# deska.net
KiCad netlist of a schematic drawn in EAGLE
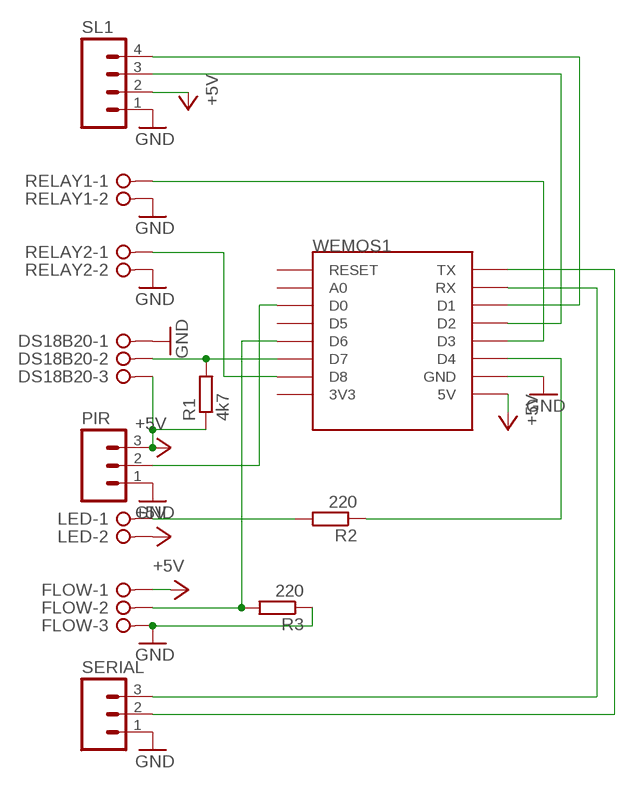
[diagram p0: schematic, sheet 1]

(export (version "E")
  (design (tool "Eeschema 10.0.6"))
  (components
    (comp (ref "DS18B20")
      (value "W237-03P")
      (footprint "eagle-import:W237-133")
      (libsource (lib "eagle-import") (part "W237-03P"))
    )
    (comp (ref "FLOW")
      (value "W237-03P")
      (footprint "eagle-import:W237-133")
      (libsource (lib "eagle-import") (part "W237-03P"))
    )
    (comp (ref "LED")
      (value "W237-02P")
      (footprint "eagle-import:W237-132")
      (libsource (lib "eagle-import") (part "W237-02P"))
    )
    (comp (ref "PIR")
      (value "M03")
      (footprint "eagle-import:03P")
      (libsource (lib "eagle-import") (part "M03"))
    )
    (comp (ref "R1")
      (value "4k7")
      (footprint "eagle-import:0207_10")
      (libsource (lib "eagle-import") (part "R-EU_0207/10"))
    )
    (comp (ref "R2")
      (value "220")
      (footprint "eagle-import:0207_10")
      (libsource (lib "eagle-import") (part "R-EU_0207/10"))
    )
    (comp (ref "R3")
      (value "220")
      (footprint "eagle-import:0207_10")
      (libsource (lib "eagle-import") (part "R-EU_0207/10"))
    )
    (comp (ref "RELAY1")
      (value "W237-02P")
      (footprint "eagle-import:W237-132")
      (libsource (lib "eagle-import") (part "W237-02P"))
    )
    (comp (ref "RELAY2")
      (value "W237-02P")
      (footprint "eagle-import:W237-132")
      (libsource (lib "eagle-import") (part "W237-02P"))
    )
    (comp (ref "SERIAL")
      (value "M03")
      (footprint "eagle-import:03P")
      (libsource (lib "eagle-import") (part "M03"))
    )
    (comp (ref "SL1")
      (value "M04")
      (footprint "eagle-import:04P")
      (libsource (lib "eagle-import") (part "M04"))
    )
    (comp (ref "WEMOS1")
      (value "WEMOS-D1-MINI")
      (footprint "eagle-import:WEMOS-D1-MINI")
      (libsource (lib "eagle-import") (part "WEMOS-D1-MINI"))
    )
  )
  (nets
    (net (code "1") (name "+5V") (class "Default")
      (node (ref "DS18B20") (pin "3") (pinfunction "KL_3") (pintype "passive"))
      (node (ref "FLOW") (pin "1") (pinfunction "KL_1") (pintype "passive"))
      (node (ref "LED") (pin "2") (pinfunction "KL_2") (pintype "passive"))
      (node (ref "PIR") (pin "3") (pinfunction "3_3") (pintype "passive"))
      (node (ref "R1") (pin "1") (pinfunction "1_1") (pintype "passive"))
      (node (ref "SL1") (pin "2") (pinfunction "2_2") (pintype "passive"))
      (node (ref "WEMOS1") (pin "5V") (pinfunction "5V_5V") (pintype "bidirectional"))
    )
    (net (code "2") (name "GND") (class "Default")
      (node (ref "DS18B20") (pin "1") (pinfunction "KL_1") (pintype "passive"))
      (node (ref "FLOW") (pin "3") (pinfunction "KL_3") (pintype "passive"))
      (node (ref "PIR") (pin "1") (pinfunction "1_1") (pintype "passive"))
      (node (ref "R3") (pin "1") (pinfunction "1_1") (pintype "passive"))
      (node (ref "RELAY1") (pin "2") (pinfunction "KL_2") (pintype "passive"))
      (node (ref "RELAY2") (pin "2") (pinfunction "KL_2") (pintype "passive"))
      (node (ref "SERIAL") (pin "1") (pinfunction "1_1") (pintype "passive"))
      (node (ref "SL1") (pin "1") (pinfunction "1_1") (pintype "passive"))
      (node (ref "WEMOS1") (pin "GND") (pinfunction "GND_GND") (pintype "bidirectional"))
    )
    (net (code "3") (name "Net-(DS18B20B-KL)") (class "Default")
      (node (ref "DS18B20") (pin "2") (pinfunction "KL_2") (pintype "passive"))
      (node (ref "R1") (pin "2") (pinfunction "2_2") (pintype "passive"))
      (node (ref "WEMOS1") (pin "D7") (pinfunction "D7_D7") (pintype "bidirectional"))
    )
    (net (code "4") (name "Net-(FLOWB-KL)") (class "Default")
      (node (ref "FLOW") (pin "2") (pinfunction "KL_2") (pintype "passive"))
      (node (ref "R3") (pin "2") (pinfunction "2_2") (pintype "passive"))
      (node (ref "WEMOS1") (pin "D6") (pinfunction "D6_D6") (pintype "bidirectional"))
    )
    (net (code "5") (name "Net-(LEDA-KL)") (class "Default")
      (node (ref "LED") (pin "1") (pinfunction "KL_1") (pintype "passive"))
      (node (ref "R2") (pin "2") (pinfunction "2_2") (pintype "passive"))
    )
    (net (code "6") (name "Net-(PIR-Pad2)") (class "Default")
      (node (ref "PIR") (pin "2") (pinfunction "2_2") (pintype "passive"))
      (node (ref "WEMOS1") (pin "D0") (pinfunction "D0_D0") (pintype "bidirectional"))
    )
    (net (code "7") (name "Net-(R2-Pad1)") (class "Default")
      (node (ref "R2") (pin "1") (pinfunction "1_1") (pintype "passive"))
      (node (ref "WEMOS1") (pin "D4") (pinfunction "D4_D4") (pintype "bidirectional"))
    )
    (net (code "8") (name "Net-(RELAY1A-KL)") (class "Default")
      (node (ref "RELAY1") (pin "1") (pinfunction "KL_1") (pintype "passive"))
      (node (ref "WEMOS1") (pin "D3") (pinfunction "D3_D3") (pintype "bidirectional"))
    )
    (net (code "9") (name "Net-(RELAY2A-KL)") (class "Default")
      (node (ref "RELAY2") (pin "1") (pinfunction "KL_1") (pintype "passive"))
      (node (ref "WEMOS1") (pin "D8") (pinfunction "D8_D8") (pintype "bidirectional"))
    )
    (net (code "10") (name "Net-(SERIAL-Pad2)") (class "Default")
      (node (ref "SERIAL") (pin "2") (pinfunction "2_2") (pintype "passive"))
      (node (ref "WEMOS1") (pin "TX") (pinfunction "TX_TX") (pintype "bidirectional"))
    )
    (net (code "11") (name "Net-(SERIAL-Pad3)") (class "Default")
      (node (ref "SERIAL") (pin "3") (pinfunction "3_3") (pintype "passive"))
      (node (ref "WEMOS1") (pin "RX") (pinfunction "RX_RX") (pintype "bidirectional"))
    )
    (net (code "12") (name "Net-(SL1-Pad3)") (class "Default")
      (node (ref "SL1") (pin "3") (pinfunction "3_3") (pintype "passive"))
      (node (ref "WEMOS1") (pin "D2") (pinfunction "D2_D2") (pintype "bidirectional"))
    )
    (net (code "13") (name "Net-(SL1-Pad4)") (class "Default")
      (node (ref "SL1") (pin "4") (pinfunction "4_4") (pintype "passive"))
      (node (ref "WEMOS1") (pin "D1") (pinfunction "D1_D1") (pintype "bidirectional"))
    )
    (net (code "14") (name "unconnected-(WEMOS1-Pad3V3)") (class "Default")
      (node (ref "WEMOS1") (pin "3V3") (pinfunction "3V3_3V3") (pintype "bidirectional"))
    )
    (net (code "15") (name "unconnected-(WEMOS1-PadA0)") (class "Default")
      (node (ref "WEMOS1") (pin "A0") (pinfunction "A0_A0") (pintype "bidirectional"))
    )
    (net (code "16") (name "unconnected-(WEMOS1-PadD5)") (class "Default")
      (node (ref "WEMOS1") (pin "D5") (pinfunction "D5_D5") (pintype "bidirectional"))
    )
    (net (code "17") (name "unconnected-(WEMOS1-PadRESET)") (class "Default")
      (node (ref "WEMOS1") (pin "RESET") (pinfunction "RESET_RESET") (pintype "bidirectional"))
    )
  )
)
